# SCH_555__2022-10-18.net
KiCad netlist of a schematic drawn in EasyEDA
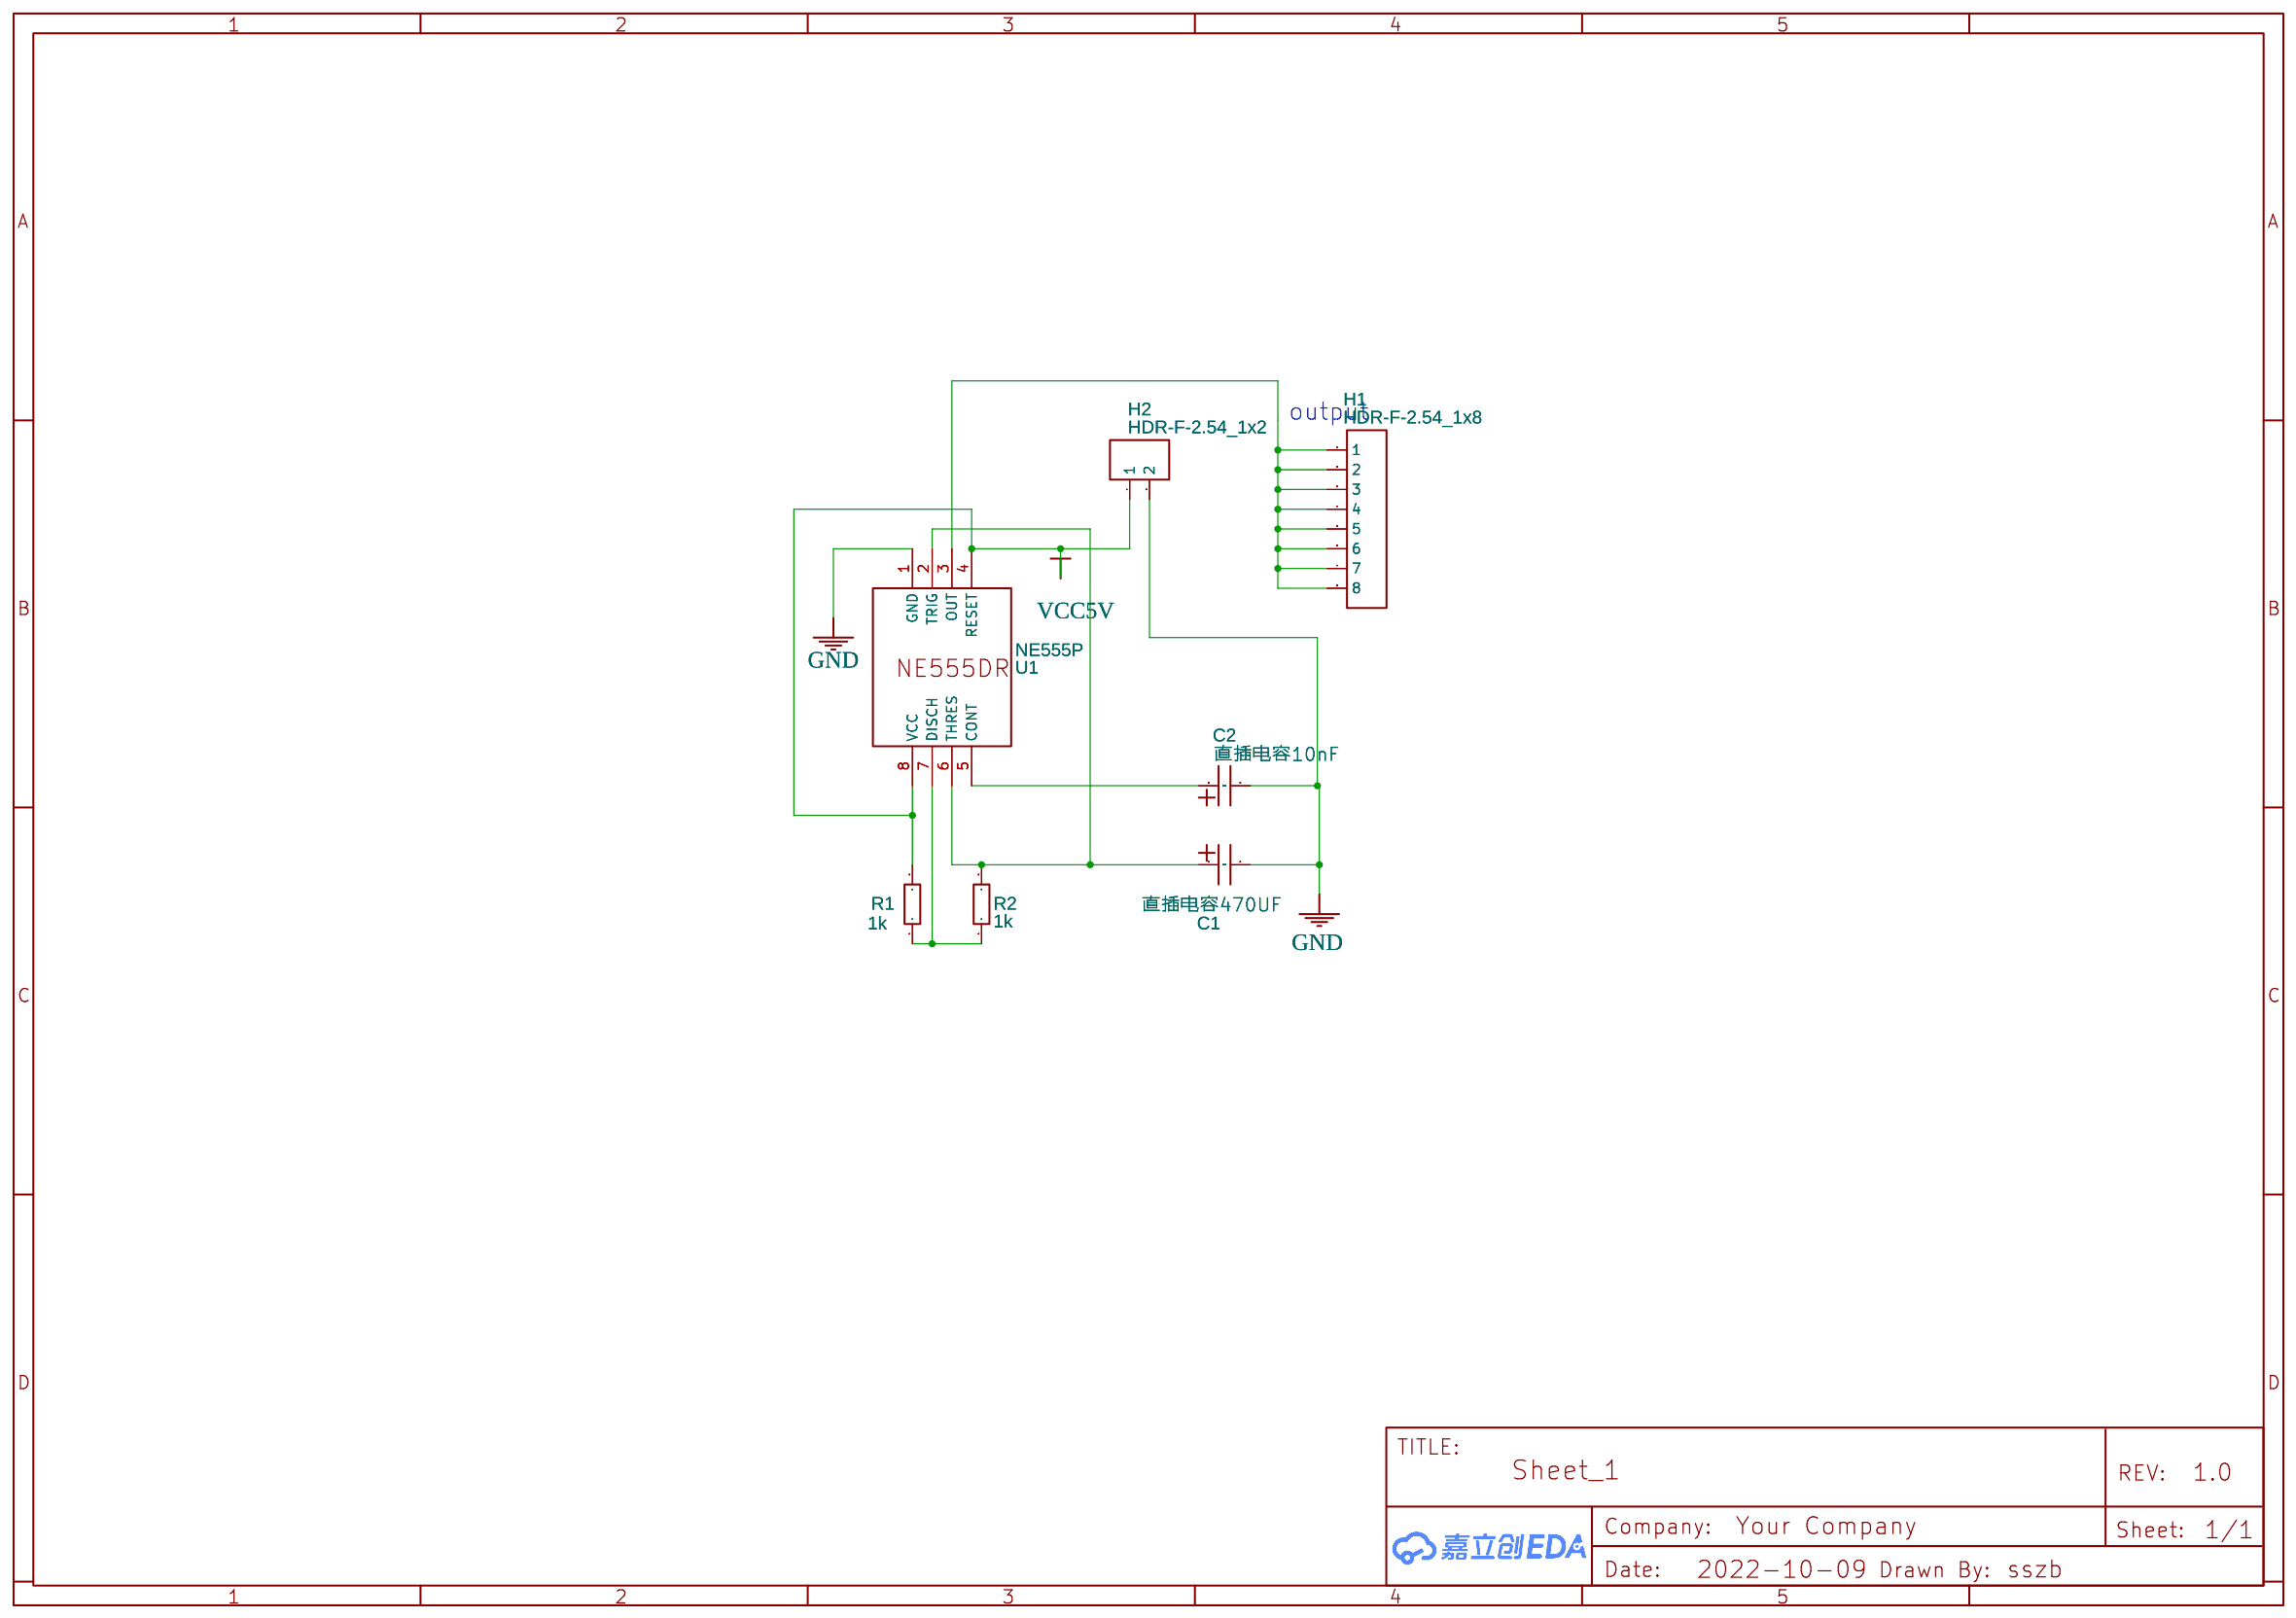
[diagram p0: schematic sheet]

(export (version "E")
  (design (tool "Eeschema 10.0.6"))
  (components
    (comp (ref "C1") (value "直插电容470UF") (libsource (lib "") (part "直插电容470UF")))
    (comp (ref "C2") (value "直插电容10nF") (libsource (lib "") (part "直插电容470UF_1")))
    (comp (ref "H1")
      (value "HDR-F-2.54_1x8")
      (fields (field (name "BOM_Supplier Part") "C225505"))
      (libsource (lib "") (part "HDR-F-2.54_1x8"))
    )
    (comp (ref "H2")
      (value "HDR-F-2.54_1x2")
      (fields (field (name "BOM_Supplier Part") "C49661"))
      (libsource (lib "") (part "HDR-F-2.54_1x2"))
    )
    (comp (ref "R1")
      (value "1k")
      (fields
        (field (name "BOM_Manufacturer Part") "CFR0W4J0681A50")
        (field (name "BOM_Supplier Part") "C70784")
      )
      (libsource (lib "") (part "直插电阻"))
    )
    (comp (ref "R2")
      (value "1k")
      (fields
        (field (name "BOM_Manufacturer Part") "CFR0W4J0681A50")
        (field (name "BOM_Supplier Part") "C70784")
      )
      (libsource (lib "") (part "直插电阻"))
    )
    (comp (ref "U1") (value "NE555P") (libsource (lib "") (part "NE555P")))
  )
  (nets
    (net (code "1") (name "GND") (class "Default")
      (node (ref "C1") (pin "2") (pinfunction "2_2") (pintype "unspecified"))
      (node (ref "C2") (pin "2") (pinfunction "2_2") (pintype "unspecified"))
      (node (ref "H2") (pin "2") (pinfunction "2_2") (pintype "input"))
      (node (ref "U1") (pin "1") (pinfunction "GND_1") (pintype "unspecified"))
    )
    (net (code "2") (name "Net-(U1-CONT)") (class "Default")
      (node (ref "C2") (pin "1") (pinfunction "1_1") (pintype "unspecified"))
      (node (ref "U1") (pin "5") (pinfunction "CONT_5") (pintype "unspecified"))
    )
    (net (code "3") (name "Net-(U1-DISCH)") (class "Default")
      (node (ref "R1") (pin "1") (pinfunction "1_1") (pintype "input"))
      (node (ref "R2") (pin "1") (pinfunction "1_1") (pintype "input"))
      (node (ref "U1") (pin "7") (pinfunction "DISCH_7") (pintype "unspecified"))
    )
    (net (code "4") (name "Net-(U1-OUT)") (class "Default")
      (node (ref "H1") (pin "1") (pinfunction "1_1") (pintype "unspecified"))
      (node (ref "H1") (pin "2") (pinfunction "2_2") (pintype "unspecified"))
      (node (ref "H1") (pin "3") (pinfunction "3_3") (pintype "unspecified"))
      (node (ref "H1") (pin "4") (pinfunction "4_4") (pintype "unspecified"))
      (node (ref "H1") (pin "5") (pinfunction "5_5") (pintype "unspecified"))
      (node (ref "H1") (pin "6") (pinfunction "6_6") (pintype "unspecified"))
      (node (ref "H1") (pin "7") (pinfunction "7_7") (pintype "unspecified"))
      (node (ref "H1") (pin "8") (pinfunction "8_8") (pintype "unspecified"))
      (node (ref "U1") (pin "3") (pinfunction "OUT_3") (pintype "unspecified"))
    )
    (net (code "5") (name "Net-(U1-THRES)") (class "Default")
      (node (ref "C1") (pin "1") (pinfunction "1_1") (pintype "unspecified"))
      (node (ref "R2") (pin "2") (pinfunction "2_2") (pintype "input"))
      (node (ref "U1") (pin "2") (pinfunction "TRIG_2") (pintype "unspecified"))
      (node (ref "U1") (pin "6") (pinfunction "THRES_6") (pintype "unspecified"))
    )
    (net (code "6") (name "VCC5V") (class "Default")
      (node (ref "H2") (pin "1") (pinfunction "1_1") (pintype "input"))
      (node (ref "R1") (pin "2") (pinfunction "2_2") (pintype "input"))
      (node (ref "U1") (pin "4") (pinfunction "RESET_4") (pintype "unspecified"))
      (node (ref "U1") (pin "8") (pinfunction "VCC_8") (pintype "unspecified"))
    )
  )
)
